# MicroWordClock2.net
KiCad netlist of a schematic drawn in EAGLE
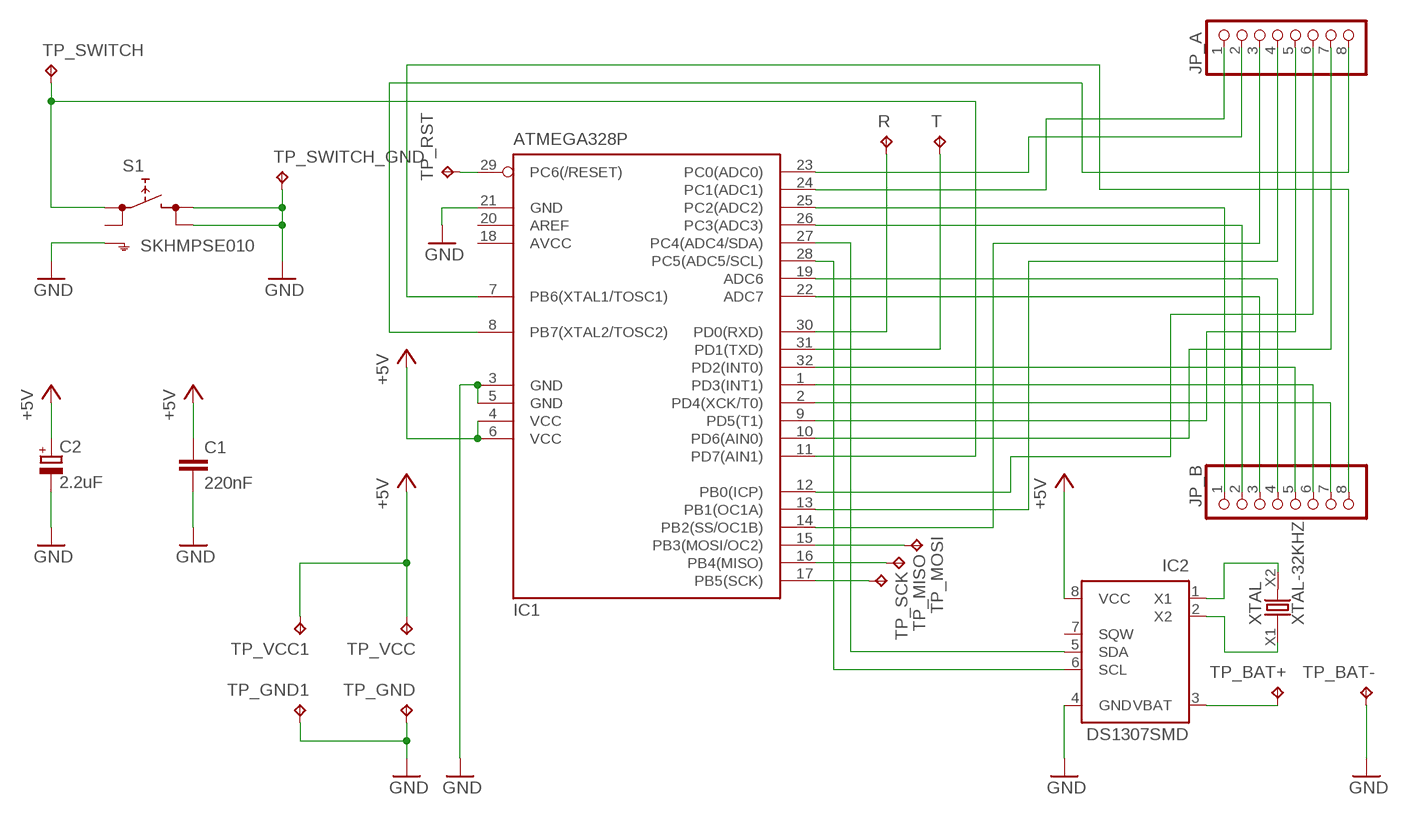
[diagram p0: schematic, sheet 1]

(export (version "E")
  (design (tool "Eeschema 10.0.6"))
  (components
    (comp (ref "C1")
      (value "220nF")
      (footprint "eagle-import:C0805")
      (libsource (lib "eagle-import") (part "C-EUC0805"))
    )
    (comp (ref "C2")
      (value "2.2uF")
      (footprint "eagle-import:B_3528-21R")
      (libsource (lib "eagle-import") (part "CPOL-EUB/3528-21R"))
    )
    (comp (ref "IC1")
      (value "ATMEGA328P")
      (footprint "eagle-import:TQFP32-08")
      (fields (field (name "MPN") "ATMEGA8-16AU"))
      (libsource (lib "eagle-import") (part "MEGA8-AI"))
    )
    (comp (ref "IC2")
      (value "DS1307SMD")
      (footprint "eagle-import:SO-08M")
      (libsource (lib "eagle-import") (part "DS1307SMD"))
    )
    (comp (ref "JP_A")
      (value "PINHD-1X8CLEANBIG")
      (footprint "eagle-import:1X08-CLEANBIG")
      (libsource (lib "eagle-import") (part "PINHD-1X8CLEANBIG"))
    )
    (comp (ref "JP_B")
      (value "PINHD-1X8CLEANBIG")
      (footprint "eagle-import:1X08-CLEANBIG")
      (libsource (lib "eagle-import") (part "PINHD-1X8CLEANBIG"))
    )
    (comp (ref "R")
      (value "TPB1,27")
      (footprint "eagle-import:B1,27")
      (libsource (lib "eagle-import") (part "TPB1,27"))
    )
    (comp (ref "S1")
      (value "SKHMPSE010")
      (footprint "eagle-import:SKHMPXE010")
      (libsource (lib "eagle-import") (part "SKHMPE010S"))
    )
    (comp (ref "T")
      (value "TPB1,27")
      (footprint "eagle-import:B1,27")
      (libsource (lib "eagle-import") (part "TPB1,27"))
    )
    (comp (ref "TP_BAT+")
      (value "TPB2,54")
      (footprint "eagle-import:B2,54")
      (libsource (lib "eagle-import") (part "TPB2,54"))
    )
    (comp (ref "TP_BAT-")
      (value "TPB2,54")
      (footprint "eagle-import:B2,54")
      (libsource (lib "eagle-import") (part "TPB2,54"))
    )
    (comp (ref "TP_GND")
      (value "TPB1,27")
      (footprint "eagle-import:B1,27")
      (libsource (lib "eagle-import") (part "TPB1,27"))
    )
    (comp (ref "TP_GND1")
      (value "TPB2,54")
      (footprint "eagle-import:B2,54")
      (libsource (lib "eagle-import") (part "TPB2,54"))
    )
    (comp (ref "TP_MISO")
      (value "TPB1,27")
      (footprint "eagle-import:B1,27")
      (libsource (lib "eagle-import") (part "TPB1,27"))
    )
    (comp (ref "TP_MOSI")
      (value "TPB1,27")
      (footprint "eagle-import:B1,27")
      (libsource (lib "eagle-import") (part "TPB1,27"))
    )
    (comp (ref "TP_RST")
      (value "TPB1,27")
      (footprint "eagle-import:B1,27")
      (libsource (lib "eagle-import") (part "TPB1,27"))
    )
    (comp (ref "TP_SCK")
      (value "TPB1,27")
      (footprint "eagle-import:B1,27")
      (libsource (lib "eagle-import") (part "TPB1,27"))
    )
    (comp (ref "TP_SWITCH")
      (value "TPB1,27")
      (footprint "eagle-import:B1,27")
      (libsource (lib "eagle-import") (part "TPB1,27"))
    )
    (comp (ref "TP_SWITCH_GND")
      (value "TPB1,27")
      (footprint "eagle-import:B1,27")
      (libsource (lib "eagle-import") (part "TPB1,27"))
    )
    (comp (ref "TP_VCC")
      (value "TPB1,27")
      (footprint "eagle-import:B1,27")
      (libsource (lib "eagle-import") (part "TPB1,27"))
    )
    (comp (ref "TP_VCC1")
      (value "TPB2,54")
      (footprint "eagle-import:B2,54")
      (libsource (lib "eagle-import") (part "TPB2,54"))
    )
    (comp (ref "XTAL")
      (value "XTAL-32KHZ")
      (footprint "eagle-import:XTAL-SMD-1206-3216M")
      (libsource (lib "eagle-import") (part "XTAL-32KHZ"))
    )
  )
  (nets
    (net (code "1") (name "+5V") (class "Default")
      (node (ref "C1") (pin "1") (pinfunction "1_1") (pintype "passive"))
      (node (ref "C2") (pin "+") (pinfunction "+_+") (pintype "passive"))
      (node (ref "IC1") (pin "4") (pinfunction "VCC_4") (pintype "power_in"))
      (node (ref "IC1") (pin "6") (pinfunction "VCC_6") (pintype "power_in"))
      (node (ref "IC2") (pin "8") (pinfunction "VCC_8") (pintype "power_in"))
      (node (ref "TP_VCC") (pin "TP") (pinfunction "TP_TP") (pintype "input"))
      (node (ref "TP_VCC1") (pin "TP") (pinfunction "TP_TP") (pintype "input"))
    )
    (net (code "2") (name "/AVCC") (class "Default")
      (node (ref "IC1") (pin "18") (pinfunction "AVCC_18") (pintype "power_in"))
    )
    (net (code "3") (name "GND") (class "Default")
      (node (ref "C1") (pin "2") (pinfunction "2_2") (pintype "passive"))
      (node (ref "C2") (pin "-") (pinfunction "-_-") (pintype "passive"))
      (node (ref "IC1") (pin "21") (pinfunction "GND_21") (pintype "power_in"))
      (node (ref "IC1") (pin "3") (pinfunction "GND_3") (pintype "power_in"))
      (node (ref "IC1") (pin "5") (pinfunction "GND_5") (pintype "power_in"))
      (node (ref "IC2") (pin "4") (pinfunction "GND_4") (pintype "power_in"))
      (node (ref "S1") (pin "3") (pinfunction "2.1_3") (pintype "passive"))
      (node (ref "S1") (pin "4") (pinfunction "2.2_4") (pintype "passive"))
      (node (ref "S1") (pin "5") (pinfunction "SH_5") (pintype "passive"))
      (node (ref "TP_BAT-") (pin "TP") (pinfunction "TP_TP") (pintype "input"))
      (node (ref "TP_GND") (pin "TP") (pinfunction "TP_TP") (pintype "input"))
      (node (ref "TP_GND1") (pin "TP") (pinfunction "TP_TP") (pintype "input"))
      (node (ref "TP_SWITCH_GND") (pin "TP") (pinfunction "TP_TP") (pintype "input"))
    )
    (net (code "4") (name "Net-(IC1-ADC6)") (class "Default")
      (node (ref "IC1") (pin "19") (pinfunction "ADC6_19") (pintype "bidirectional"))
      (node (ref "JP_B") (pin "4") (pinfunction "4_4") (pintype "passive"))
    )
    (net (code "5") (name "Net-(IC1-ADC7)") (class "Default")
      (node (ref "IC1") (pin "22") (pinfunction "ADC7_22") (pintype "bidirectional"))
      (node (ref "JP_B") (pin "3") (pinfunction "3_3") (pintype "passive"))
    )
    (net (code "6") (name "Net-(IC1-PB0(ICP))") (class "Default")
      (node (ref "IC1") (pin "12") (pinfunction "PB0(ICP)_12") (pintype "bidirectional"))
      (node (ref "JP_A") (pin "6") (pinfunction "6_6") (pintype "passive"))
    )
    (net (code "7") (name "Net-(IC1-PB1(OC1A))") (class "Default")
      (node (ref "IC1") (pin "13") (pinfunction "PB1(OC1A)_13") (pintype "bidirectional"))
      (node (ref "JP_A") (pin "4") (pinfunction "4_4") (pintype "passive"))
    )
    (net (code "8") (name "Net-(IC1-PB2(SS{slash}OC1B))") (class "Default")
      (node (ref "IC1") (pin "14") (pinfunction "PB2(SS/OC1B)_14") (pintype "bidirectional"))
      (node (ref "JP_A") (pin "3") (pinfunction "3_3") (pintype "passive"))
    )
    (net (code "9") (name "Net-(IC1-PB3(MOSI{slash}OC2))") (class "Default")
      (node (ref "IC1") (pin "15") (pinfunction "PB3(MOSI/OC2)_15") (pintype "bidirectional"))
      (node (ref "TP_MOSI") (pin "TP") (pinfunction "TP_TP") (pintype "input"))
    )
    (net (code "10") (name "Net-(IC1-PB4(MISO))") (class "Default")
      (node (ref "IC1") (pin "16") (pinfunction "PB4(MISO)_16") (pintype "bidirectional"))
      (node (ref "TP_MISO") (pin "TP") (pinfunction "TP_TP") (pintype "input"))
    )
    (net (code "11") (name "Net-(IC1-PB5(SCK))") (class "Default")
      (node (ref "IC1") (pin "17") (pinfunction "PB5(SCK)_17") (pintype "bidirectional"))
      (node (ref "TP_SCK") (pin "TP") (pinfunction "TP_TP") (pintype "input"))
    )
    (net (code "12") (name "Net-(IC1-PB6(XTAL1{slash}TOSC1))") (class "Default")
      (node (ref "IC1") (pin "7") (pinfunction "PB6(XTAL1/TOSC1)_7") (pintype "bidirectional"))
      (node (ref "JP_B") (pin "8") (pinfunction "8_8") (pintype "passive"))
    )
    (net (code "13") (name "Net-(IC1-PB7(XTAL2{slash}TOSC2))") (class "Default")
      (node (ref "IC1") (pin "8") (pinfunction "PB7(XTAL2/TOSC2)_8") (pintype "bidirectional"))
      (node (ref "JP_A") (pin "8") (pinfunction "8_8") (pintype "passive"))
    )
    (net (code "14") (name "Net-(IC1-PC0(ADC0))") (class "Default")
      (node (ref "IC1") (pin "23") (pinfunction "PC0(ADC0)_23") (pintype "bidirectional"))
      (node (ref "JP_A") (pin "2") (pinfunction "2_2") (pintype "passive"))
    )
    (net (code "15") (name "Net-(IC1-PC1(ADC1))") (class "Default")
      (node (ref "IC1") (pin "24") (pinfunction "PC1(ADC1)_24") (pintype "bidirectional"))
      (node (ref "JP_A") (pin "1") (pinfunction "1_1") (pintype "passive"))
    )
    (net (code "16") (name "Net-(IC1-PC2(ADC2))") (class "Default")
      (node (ref "IC1") (pin "25") (pinfunction "PC2(ADC2)_25") (pintype "bidirectional"))
      (node (ref "JP_B") (pin "1") (pinfunction "1_1") (pintype "passive"))
    )
    (net (code "17") (name "Net-(IC1-PC3(ADC3))") (class "Default")
      (node (ref "IC1") (pin "26") (pinfunction "PC3(ADC3)_26") (pintype "bidirectional"))
      (node (ref "JP_B") (pin "2") (pinfunction "2_2") (pintype "passive"))
    )
    (net (code "18") (name "Net-(IC1-PC4(ADC4{slash}SDA))") (class "Default")
      (node (ref "IC1") (pin "27") (pinfunction "PC4(ADC4/SDA)_27") (pintype "bidirectional"))
      (node (ref "IC2") (pin "5") (pinfunction "SDA_5") (pintype "output"))
    )
    (net (code "19") (name "Net-(IC1-PC5(ADC5{slash}SCL))") (class "Default")
      (node (ref "IC1") (pin "28") (pinfunction "PC5(ADC5/SCL)_28") (pintype "bidirectional"))
      (node (ref "IC2") (pin "6") (pinfunction "SCL_6") (pintype "input"))
    )
    (net (code "20") (name "Net-(IC1-PC6({slash}RESET))") (class "Default")
      (node (ref "IC1") (pin "29") (pinfunction "PC6(/RESET)_29") (pintype "bidirectional"))
      (node (ref "TP_RST") (pin "TP") (pinfunction "TP_TP") (pintype "input"))
    )
    (net (code "21") (name "Net-(IC1-PD0(RXD))") (class "Default")
      (node (ref "IC1") (pin "30") (pinfunction "PD0(RXD)_30") (pintype "bidirectional"))
      (node (ref "R") (pin "TP") (pinfunction "TP_TP") (pintype "input"))
    )
    (net (code "22") (name "Net-(IC1-PD1(TXD))") (class "Default")
      (node (ref "IC1") (pin "31") (pinfunction "PD1(TXD)_31") (pintype "bidirectional"))
      (node (ref "T") (pin "TP") (pinfunction "TP_TP") (pintype "input"))
    )
    (net (code "23") (name "Net-(IC1-PD2(INT0))") (class "Default")
      (node (ref "IC1") (pin "32") (pinfunction "PD2(INT0)_32") (pintype "bidirectional"))
      (node (ref "JP_B") (pin "5") (pinfunction "5_5") (pintype "passive"))
    )
    (net (code "24") (name "Net-(IC1-PD3(INT1))") (class "Default")
      (node (ref "IC1") (pin "1") (pinfunction "PD3(INT1)_1") (pintype "bidirectional"))
      (node (ref "JP_B") (pin "6") (pinfunction "6_6") (pintype "passive"))
    )
    (net (code "25") (name "Net-(IC1-PD4(XCK{slash}T0))") (class "Default")
      (node (ref "IC1") (pin "2") (pinfunction "PD4(XCK/T0)_2") (pintype "bidirectional"))
      (node (ref "JP_B") (pin "7") (pinfunction "7_7") (pintype "passive"))
    )
    (net (code "26") (name "Net-(IC1-PD5(T1))") (class "Default")
      (node (ref "IC1") (pin "9") (pinfunction "PD5(T1)_9") (pintype "bidirectional"))
      (node (ref "JP_A") (pin "5") (pinfunction "5_5") (pintype "passive"))
    )
    (net (code "27") (name "Net-(IC1-PD6(AIN0))") (class "Default")
      (node (ref "IC1") (pin "10") (pinfunction "PD6(AIN0)_10") (pintype "bidirectional"))
      (node (ref "JP_A") (pin "7") (pinfunction "7_7") (pintype "passive"))
    )
    (net (code "28") (name "Net-(IC1-PD7(AIN1))") (class "Default")
      (node (ref "IC1") (pin "11") (pinfunction "PD7(AIN1)_11") (pintype "bidirectional"))
      (node (ref "S1") (pin "1") (pinfunction "1.1_1") (pintype "passive"))
      (node (ref "TP_SWITCH") (pin "TP") (pinfunction "TP_TP") (pintype "input"))
    )
    (net (code "29") (name "Net-(IC2-VBAT)") (class "Default")
      (node (ref "IC2") (pin "3") (pinfunction "VBAT_3") (pintype "input"))
      (node (ref "TP_BAT+") (pin "TP") (pinfunction "TP_TP") (pintype "input"))
    )
    (net (code "30") (name "Net-(IC2-X1)") (class "Default")
      (node (ref "IC2") (pin "1") (pinfunction "X1_1") (pintype "input"))
      (node (ref "XTAL") (pin "X2") (pinfunction "X2_X2") (pintype "passive"))
    )
    (net (code "31") (name "Net-(IC2-X2)") (class "Default")
      (node (ref "IC2") (pin "2") (pinfunction "X2_2") (pintype "input"))
      (node (ref "XTAL") (pin "X1") (pinfunction "X1_X1") (pintype "passive"))
    )
    (net (code "32") (name "unconnected-(IC1-AREF-Pad20)") (class "Default")
      (node (ref "IC1") (pin "20") (pinfunction "AREF_20") (pintype "passive"))
    )
    (net (code "33") (name "unconnected-(IC2-SQW-Pad7)") (class "Default")
      (node (ref "IC2") (pin "7") (pinfunction "SQW_7") (pintype "input"))
    )
    (net (code "34") (name "unconnected-(S1-1.2-Pad2)") (class "Default")
      (node (ref "S1") (pin "2") (pinfunction "1.2_2") (pintype "passive"))
    )
  )
)
